# 8_sata.net
KiCad netlist of a schematic drawn in Altium Designer
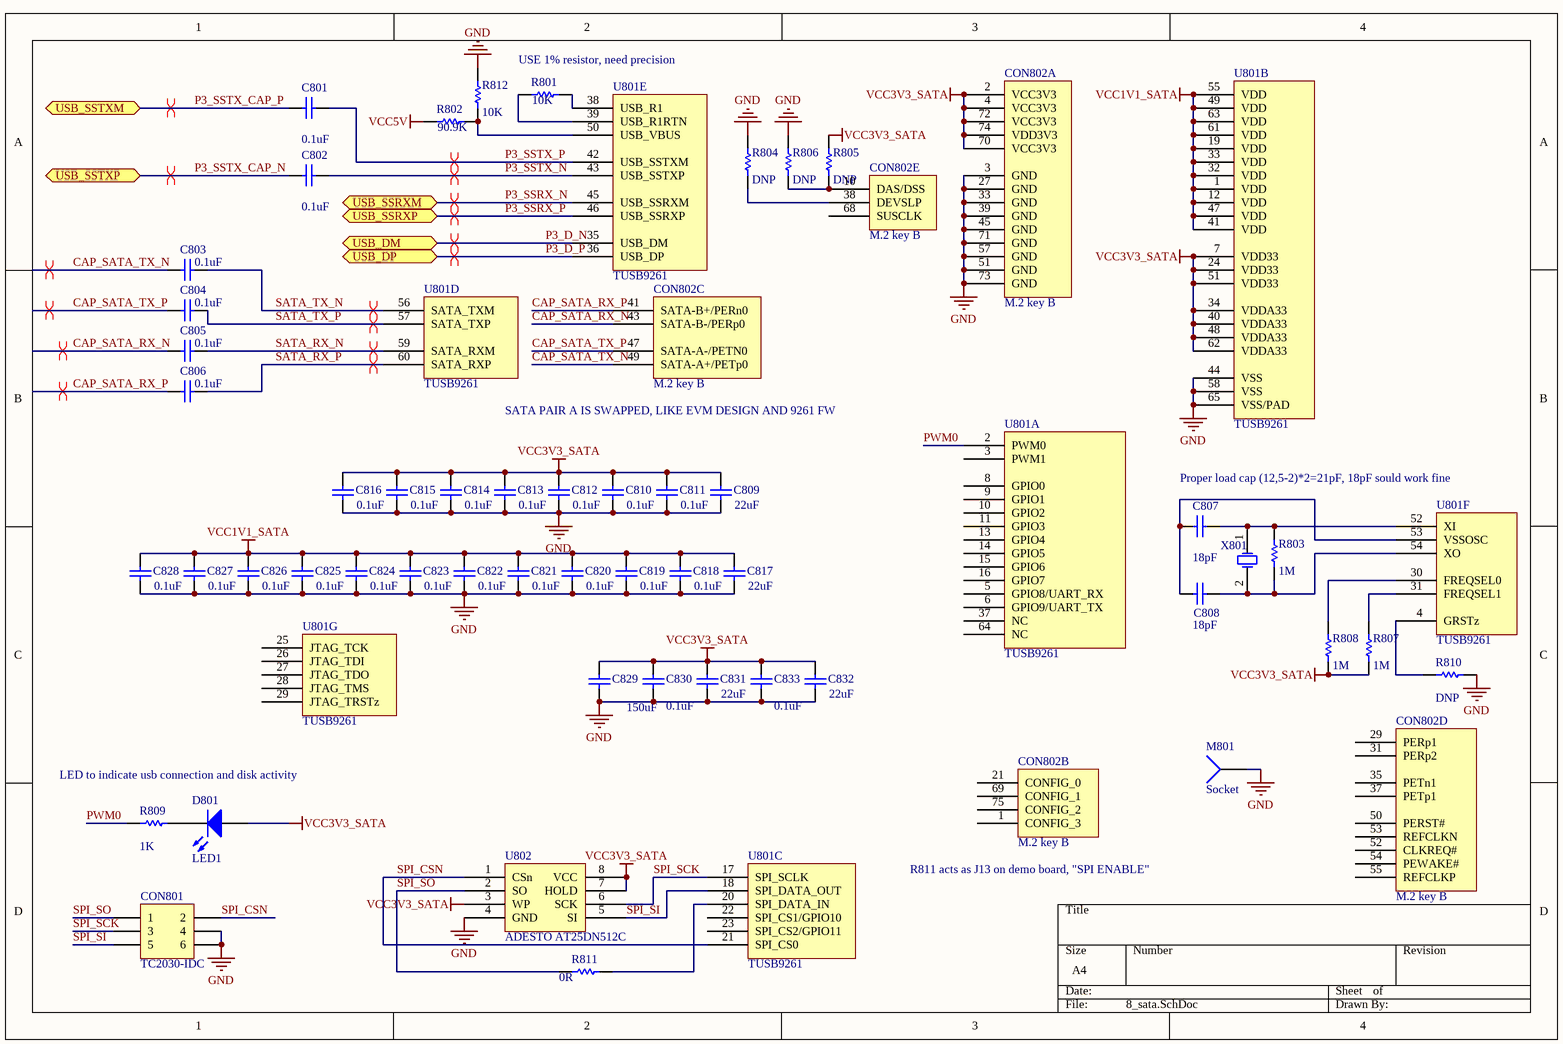
[diagram p0: 8_sata.SchDoc]

(export (version "E")
  (design (tool "Eeschema 10.0.6"))
  (components
    (comp (ref "C801")
      (value "0.1uF")
      (footprint "C0402[1005]")
      (description "Capacitor")
      (fields (field (name "MFG") "KEMET"))
      (libsource (lib "Miscellaneous Devices") (part "Cap"))
    )
    (comp (ref "C802")
      (value "0.1uF")
      (footprint "C0402[1005]")
      (description "Capacitor")
      (fields (field (name "MFG") "KEMET"))
      (libsource (lib "Miscellaneous Devices") (part "Cap"))
    )
    (comp (ref "C803")
      (value "0.1uF")
      (footprint "C0402[1005]")
      (description "Capacitor")
      (fields (field (name "MFG") "KEMET"))
      (libsource (lib "Miscellaneous Devices") (part "Cap"))
    )
    (comp (ref "C804")
      (value "0.1uF")
      (footprint "C0402[1005]")
      (description "Capacitor")
      (fields (field (name "MFG") "KEMET"))
      (libsource (lib "Miscellaneous Devices") (part "Cap"))
    )
    (comp (ref "C805")
      (value "0.1uF")
      (footprint "C0402[1005]")
      (description "Capacitor")
      (fields (field (name "MFG") "KEMET"))
      (libsource (lib "Miscellaneous Devices") (part "Cap"))
    )
    (comp (ref "C806")
      (value "0.1uF")
      (footprint "C0402[1005]")
      (description "Capacitor")
      (fields (field (name "MFG") "KEMET"))
      (libsource (lib "Miscellaneous Devices") (part "Cap"))
    )
    (comp (ref "C807")
      (value "18pF")
      (footprint "C0603[1608]")
      (description "Capacitor")
      (fields (field (name "MFG") "KEMET"))
      (libsource (lib "Miscellaneous Devices") (part "Cap"))
    )
    (comp (ref "C808")
      (value "18pF")
      (footprint "C0603[1608]")
      (description "Capacitor")
      (fields (field (name "MFG") "KEMET"))
      (libsource (lib "Miscellaneous Devices") (part "Cap"))
    )
    (comp (ref "C809")
      (value "22uF")
      (footprint "C1206[3216]")
      (description "Capacitor")
      (fields (field (name "MFG") "KEMET"))
      (libsource (lib "Miscellaneous Devices") (part "Cap"))
    )
    (comp (ref "C810")
      (value "0.1uF")
      (footprint "C0603[1608]")
      (description "Capacitor")
      (fields (field (name "MFG") "KEMET"))
      (libsource (lib "Miscellaneous Devices") (part "Cap"))
    )
    (comp (ref "C811")
      (value "0.1uF")
      (footprint "C0603[1608]")
      (description "Capacitor")
      (fields (field (name "MFG") "KEMET"))
      (libsource (lib "Miscellaneous Devices") (part "Cap"))
    )
    (comp (ref "C812")
      (value "0.1uF")
      (footprint "C0603[1608]")
      (description "Capacitor")
      (fields (field (name "MFG") "KEMET"))
      (libsource (lib "Miscellaneous Devices") (part "Cap"))
    )
    (comp (ref "C813")
      (value "0.1uF")
      (footprint "C0603[1608]")
      (description "Capacitor")
      (fields (field (name "MFG") "KEMET"))
      (libsource (lib "Miscellaneous Devices") (part "Cap"))
    )
    (comp (ref "C814")
      (value "0.1uF")
      (footprint "C0603[1608]")
      (description "Capacitor")
      (fields (field (name "MFG") "KEMET"))
      (libsource (lib "Miscellaneous Devices") (part "Cap"))
    )
    (comp (ref "C815")
      (value "0.1uF")
      (footprint "C0603[1608]")
      (description "Capacitor")
      (fields (field (name "MFG") "KEMET"))
      (libsource (lib "Miscellaneous Devices") (part "Cap"))
    )
    (comp (ref "C816")
      (value "0.1uF")
      (footprint "C0603[1608]")
      (description "Capacitor")
      (fields (field (name "MFG") "KEMET"))
      (libsource (lib "Miscellaneous Devices") (part "Cap"))
    )
    (comp (ref "C817")
      (value "22uF")
      (footprint "C1206[3216]")
      (description "Capacitor")
      (fields (field (name "MFG") "KEMET"))
      (libsource (lib "Miscellaneous Devices") (part "Cap"))
    )
    (comp (ref "C818")
      (value "0.1uF")
      (footprint "C0603[1608]")
      (description "Capacitor")
      (fields (field (name "MFG") "KEMET"))
      (libsource (lib "Miscellaneous Devices") (part "Cap"))
    )
    (comp (ref "C819")
      (value "0.1uF")
      (footprint "C0603[1608]")
      (description "Capacitor")
      (fields (field (name "MFG") "KEMET"))
      (libsource (lib "Miscellaneous Devices") (part "Cap"))
    )
    (comp (ref "C820")
      (value "0.1uF")
      (footprint "C0603[1608]")
      (description "Capacitor")
      (fields (field (name "MFG") "KEMET"))
      (libsource (lib "Miscellaneous Devices") (part "Cap"))
    )
    (comp (ref "C821")
      (value "0.1uF")
      (footprint "C0603[1608]")
      (description "Capacitor")
      (fields (field (name "MFG") "KEMET"))
      (libsource (lib "Miscellaneous Devices") (part "Cap"))
    )
    (comp (ref "C822")
      (value "0.1uF")
      (footprint "C0603[1608]")
      (description "Capacitor")
      (fields (field (name "MFG") "KEMET"))
      (libsource (lib "Miscellaneous Devices") (part "Cap"))
    )
    (comp (ref "C823")
      (value "0.1uF")
      (footprint "C0603[1608]")
      (description "Capacitor")
      (fields (field (name "MFG") "KEMET"))
      (libsource (lib "Miscellaneous Devices") (part "Cap"))
    )
    (comp (ref "C824")
      (value "0.1uF")
      (footprint "C0603[1608]")
      (description "Capacitor")
      (fields (field (name "MFG") "KEMET"))
      (libsource (lib "Miscellaneous Devices") (part "Cap"))
    )
    (comp (ref "C825")
      (value "0.1uF")
      (footprint "C0603[1608]")
      (description "Capacitor")
      (fields (field (name "MFG") "KEMET"))
      (libsource (lib "Miscellaneous Devices") (part "Cap"))
    )
    (comp (ref "C826")
      (value "0.1uF")
      (footprint "C0603[1608]")
      (description "Capacitor")
      (fields (field (name "MFG") "KEMET"))
      (libsource (lib "Miscellaneous Devices") (part "Cap"))
    )
    (comp (ref "C827")
      (value "0.1uF")
      (footprint "C0603[1608]")
      (description "Capacitor")
      (fields (field (name "MFG") "KEMET"))
      (libsource (lib "Miscellaneous Devices") (part "Cap"))
    )
    (comp (ref "C828")
      (value "0.1uF")
      (footprint "C0603[1608]")
      (description "Capacitor")
      (fields (field (name "MFG") "KEMET"))
      (libsource (lib "Miscellaneous Devices") (part "Cap"))
    )
    (comp (ref "C829")
      (value "150uF")
      (footprint "C_9G_9H")
      (description "Capacitor")
      (fields (field (name "MFG") "United Chemi-Con"))
      (libsource (lib "Miscellaneous Devices") (part "Cap"))
    )
    (comp (ref "C830")
      (value "0.1uF")
      (footprint "C0603[1608]")
      (description "Capacitor")
      (fields (field (name "MFG") "KEMET"))
      (libsource (lib "Miscellaneous Devices") (part "Cap"))
    )
    (comp (ref "C831")
      (value "22uF")
      (footprint "C1206[3216]")
      (description "Capacitor")
      (fields (field (name "MFG") "KEMET"))
      (libsource (lib "Miscellaneous Devices") (part "Cap"))
    )
    (comp (ref "C832")
      (value "22uF")
      (footprint "C1206[3216]")
      (description "Capacitor")
      (fields (field (name "MFG") "KEMET"))
      (libsource (lib "Miscellaneous Devices") (part "Cap"))
    )
    (comp (ref "C833")
      (value "0.1uF")
      (footprint "C0603[1608]")
      (description "Capacitor")
      (fields (field (name "MFG") "KEMET"))
      (libsource (lib "Miscellaneous Devices") (part "Cap"))
    )
    (comp (ref "CON801")
      (value "TC2030-IDC")
      (footprint "TC2030-IDC-NL")
      (description "Header, 3-Pin, Dual row")
      (fields (field (name "MFG") "No BOM"))
      (libsource (lib "Miscellaneous Connectors") (part "Header 3X2"))
    )
    (comp (ref "CON802")
      (value "M.2 key B")
      (footprint "Amphenol 10128796")
      (fields (field (name "MFG") "Amphenol ICC (FCI)"))
      (libsource (lib "lib") (part "M.2 key B"))
    )
    (comp (ref "D801")
      (value "LED1")
      (footprint "LED0603[1608]")
      (description "Typical RED GaAs LED")
      (fields (field (name "MFG") "Kingbright"))
      (libsource (lib "Miscellaneous Devices") (part "LED1"))
    )
    (comp (ref "M801")
      (value "Socket")
      (footprint "Wurth  9774060243R")
      (fields (field (name "MFG") "Würth Elektronik"))
      (libsource (lib "Miscellaneous Connectors") (part "Socket"))
    )
    (comp (ref "R801")
      (value "10K")
      (footprint "R0603[1608]")
      (description "Resistor")
      (fields (field (name "MFG") "Vishay Dale"))
      (libsource (lib "Miscellaneous Devices") (part "Res1"))
    )
    (comp (ref "R802")
      (value "90.9K")
      (footprint "R0603[1608]")
      (description "Resistor")
      (fields (field (name "MFG") "Vishay Dale"))
      (libsource (lib "Miscellaneous Devices") (part "Res1"))
    )
    (comp (ref "R803")
      (value "1M")
      (footprint "R0603[1608]")
      (description "Resistor")
      (fields (field (name "MFG") "Vishay Dale"))
      (libsource (lib "Miscellaneous Devices") (part "Res1"))
    )
    (comp (ref "R804")
      (value "DNP")
      (footprint "R0603[1608]")
      (description "Resistor")
      (fields (field (name "MFG") "Vishay Dale"))
      (libsource (lib "Miscellaneous Devices") (part "Res1"))
    )
    (comp (ref "R805")
      (value "DNP")
      (footprint "R0603[1608]")
      (description "Resistor")
      (fields (field (name "MFG") "Vishay Dale"))
      (libsource (lib "Miscellaneous Devices") (part "Res1"))
    )
    (comp (ref "R806")
      (value "DNP")
      (footprint "R0603[1608]")
      (description "Resistor")
      (fields (field (name "MFG") "Vishay Dale"))
      (libsource (lib "Miscellaneous Devices") (part "Res1"))
    )
    (comp (ref "R807")
      (value "1M")
      (footprint "R0603[1608]")
      (description "Resistor")
      (fields (field (name "MFG") "Vishay Dale"))
      (libsource (lib "Miscellaneous Devices") (part "Res1"))
    )
    (comp (ref "R808")
      (value "1M")
      (footprint "R0603[1608]")
      (description "Resistor")
      (fields (field (name "MFG") "Vishay Dale"))
      (libsource (lib "Miscellaneous Devices") (part "Res1"))
    )
    (comp (ref "R809")
      (value "1K")
      (footprint "R0603[1608]")
      (description "Resistor")
      (fields (field (name "MFG") "Vishay Dale"))
      (libsource (lib "Miscellaneous Devices") (part "Res1"))
    )
    (comp (ref "R810")
      (value "DNP")
      (footprint "R0603[1608]")
      (description "Resistor")
      (fields (field (name "MFG") "Vishay Dale"))
      (libsource (lib "Miscellaneous Devices") (part "Res1"))
    )
    (comp (ref "R811")
      (value "0R")
      (footprint "R0603[1608]")
      (description "Resistor")
      (fields (field (name "MFG") "Vishay Dale"))
      (libsource (lib "Miscellaneous Devices") (part "Res1"))
    )
    (comp (ref "R812")
      (value "10K")
      (footprint "R0603[1608]")
      (description "Resistor")
      (fields (field (name "MFG") "Vishay Dale"))
      (libsource (lib "Miscellaneous Devices") (part "Res1"))
    )
    (comp (ref "U801")
      (value "TUSB9261")
      (footprint "TUSB9261")
      (fields (field (name "MFG") "Texas Instruments"))
      (libsource (lib "lib") (part "TUSB9261"))
    )
    (comp (ref "U802")
      (value "ADESTO AT25DN512C")
      (footprint "ADESTO AT25DN512C -TSOP")
      (fields (field (name "MFG") "Adesto Technologies"))
      (libsource (lib "lib") (part "ADESTO AT25DN512C"))
    )
    (comp (ref "X801")
      (value "~")
      (footprint "CTS 445-series crystal")
      (description "Crystal Oscillator")
      (fields (field (name "MFG") "TXC CORPORATION"))
      (libsource (lib "Miscellaneous Devices") (part "XTAL"))
    )
  )
  (nets
    (net (code "1") (name "/CAP_SATA_RX_N") (class "Default")
      (node (ref "C805") (pin "2") (pinfunction "2_2") (pintype "passive"))
      (node (ref "CON802") (pin "43") (pinfunction "SATA-B-/PERp0_43") (pintype "passive"))
    )
    (net (code "2") (name "/CAP_SATA_RX_P") (class "Default")
      (node (ref "C806") (pin "2") (pinfunction "2_2") (pintype "passive"))
      (node (ref "CON802") (pin "41") (pinfunction "SATA-B+/PERn0_41") (pintype "passive"))
    )
    (net (code "3") (name "/CAP_SATA_TX_N") (class "Default")
      (node (ref "C803") (pin "2") (pinfunction "2_2") (pintype "passive"))
      (node (ref "CON802") (pin "49") (pinfunction "SATA-A+/PETp0_49") (pintype "passive"))
    )
    (net (code "4") (name "/CAP_SATA_TX_P") (class "Default")
      (node (ref "C804") (pin "2") (pinfunction "2_2") (pintype "passive"))
      (node (ref "CON802") (pin "47") (pinfunction "SATA-A-/PETN0_47") (pintype "passive"))
    )
    (net (code "5") (name "/P3_D_N") (class "Default")
      (node (ref "U801") (pin "35") (pinfunction "USB_DM_35") (pintype "passive"))
    )
    (net (code "6") (name "/P3_D_P") (class "Default")
      (node (ref "U801") (pin "36") (pinfunction "USB_DP_36") (pintype "passive"))
    )
    (net (code "7") (name "/P3_SSRX_N") (class "Default")
      (node (ref "U801") (pin "45") (pinfunction "USB_SSRXM_45") (pintype "passive"))
    )
    (net (code "8") (name "/P3_SSRX_P") (class "Default")
      (node (ref "U801") (pin "46") (pinfunction "USB_SSRXP_46") (pintype "passive"))
    )
    (net (code "9") (name "/P3_SSTX_CAP_N") (class "Default")
      (node (ref "C802") (pin "2") (pinfunction "2_2") (pintype "passive"))
    )
    (net (code "10") (name "/P3_SSTX_CAP_P") (class "Default")
      (node (ref "C801") (pin "2") (pinfunction "2_2") (pintype "passive"))
    )
    (net (code "11") (name "/P3_SSTX_N") (class "Default")
      (node (ref "C802") (pin "1") (pinfunction "1_1") (pintype "passive"))
      (node (ref "U801") (pin "43") (pinfunction "USB_SSTXP_43") (pintype "passive"))
    )
    (net (code "12") (name "/P3_SSTX_P") (class "Default")
      (node (ref "C801") (pin "1") (pinfunction "1_1") (pintype "passive"))
      (node (ref "U801") (pin "42") (pinfunction "USB_SSTXM_42") (pintype "passive"))
    )
    (net (code "13") (name "/PWM0") (class "Default")
      (node (ref "R809") (pin "1") (pinfunction "1_1") (pintype "passive"))
      (node (ref "U801") (pin "2") (pinfunction "PWM0_2") (pintype "passive"))
    )
    (net (code "14") (name "/SATA_RX_N") (class "Default")
      (node (ref "C805") (pin "1") (pinfunction "1_1") (pintype "passive"))
      (node (ref "U801") (pin "59") (pinfunction "SATA_RXM_59") (pintype "passive"))
    )
    (net (code "15") (name "/SATA_RX_P") (class "Default")
      (node (ref "C806") (pin "1") (pinfunction "1_1") (pintype "passive"))
      (node (ref "U801") (pin "60") (pinfunction "SATA_RXP_60") (pintype "passive"))
    )
    (net (code "16") (name "/SATA_TX_N") (class "Default")
      (node (ref "C803") (pin "1") (pinfunction "1_1") (pintype "passive"))
      (node (ref "U801") (pin "56") (pinfunction "SATA_TXM_56") (pintype "passive"))
    )
    (net (code "17") (name "/SATA_TX_P") (class "Default")
      (node (ref "C804") (pin "1") (pinfunction "1_1") (pintype "passive"))
      (node (ref "U801") (pin "57") (pinfunction "SATA_TXP_57") (pintype "passive"))
    )
    (net (code "18") (name "/SPI_CSN") (class "Default")
      (node (ref "CON801") (pin "2") (pinfunction "2_2") (pintype "passive"))
      (node (ref "U801") (pin "21") (pinfunction "SPI_CS0_21") (pintype "passive"))
      (node (ref "U802") (pin "1") (pinfunction "CSn_1") (pintype "passive"))
    )
    (net (code "19") (name "/SPI_SCK") (class "Default")
      (node (ref "CON801") (pin "3") (pinfunction "3_3") (pintype "passive"))
      (node (ref "U801") (pin "17") (pinfunction "SPI_SCLK_17") (pintype "passive"))
      (node (ref "U802") (pin "6") (pinfunction "SCK_6") (pintype "passive"))
    )
    (net (code "20") (name "/SPI_SI") (class "Default")
      (node (ref "CON801") (pin "5") (pinfunction "5_5") (pintype "passive"))
      (node (ref "U801") (pin "18") (pinfunction "SPI_DATA_OUT_18") (pintype "passive"))
      (node (ref "U802") (pin "5") (pinfunction "SI_5") (pintype "passive"))
    )
    (net (code "21") (name "/SPI_SO") (class "Default")
      (node (ref "CON801") (pin "1") (pinfunction "1_1") (pintype "passive"))
      (node (ref "R811") (pin "2") (pinfunction "2_2") (pintype "passive"))
      (node (ref "U802") (pin "2") (pinfunction "SO_2") (pintype "passive"))
    )
    (net (code "22") (name "GND") (class "Default")
      (node (ref "C809") (pin "1") (pinfunction "1_1") (pintype "passive"))
      (node (ref "C810") (pin "1") (pinfunction "1_1") (pintype "passive"))
      (node (ref "C811") (pin "1") (pinfunction "1_1") (pintype "passive"))
      (node (ref "C812") (pin "1") (pinfunction "1_1") (pintype "passive"))
      (node (ref "C813") (pin "1") (pinfunction "1_1") (pintype "passive"))
      (node (ref "C814") (pin "1") (pinfunction "1_1") (pintype "passive"))
      (node (ref "C815") (pin "1") (pinfunction "1_1") (pintype "passive"))
      (node (ref "C816") (pin "1") (pinfunction "1_1") (pintype "passive"))
      (node (ref "C817") (pin "1") (pinfunction "1_1") (pintype "passive"))
      (node (ref "C818") (pin "1") (pinfunction "1_1") (pintype "passive"))
      (node (ref "C819") (pin "1") (pinfunction "1_1") (pintype "passive"))
      (node (ref "C820") (pin "1") (pinfunction "1_1") (pintype "passive"))
      (node (ref "C821") (pin "1") (pinfunction "1_1") (pintype "passive"))
      (node (ref "C822") (pin "1") (pinfunction "1_1") (pintype "passive"))
      (node (ref "C823") (pin "1") (pinfunction "1_1") (pintype "passive"))
      (node (ref "C824") (pin "1") (pinfunction "1_1") (pintype "passive"))
      (node (ref "C825") (pin "1") (pinfunction "1_1") (pintype "passive"))
      (node (ref "C826") (pin "1") (pinfunction "1_1") (pintype "passive"))
      (node (ref "C827") (pin "1") (pinfunction "1_1") (pintype "passive"))
      (node (ref "C828") (pin "1") (pinfunction "1_1") (pintype "passive"))
      (node (ref "C829") (pin "1") (pinfunction "1_1") (pintype "passive"))
      (node (ref "C830") (pin "1") (pinfunction "1_1") (pintype "passive"))
      (node (ref "C831") (pin "1") (pinfunction "1_1") (pintype "passive"))
      (node (ref "C832") (pin "1") (pinfunction "1_1") (pintype "passive"))
      (node (ref "C833") (pin "1") (pinfunction "1_1") (pintype "passive"))
      (node (ref "CON801") (pin "4") (pinfunction "4_4") (pintype "passive"))
      (node (ref "CON801") (pin "6") (pinfunction "6_6") (pintype "passive"))
      (node (ref "CON802") (pin "27") (pinfunction "GND_27") (pintype "passive"))
      (node (ref "CON802") (pin "3") (pinfunction "GND_3") (pintype "passive"))
      (node (ref "CON802") (pin "33") (pinfunction "GND_33") (pintype "passive"))
      (node (ref "CON802") (pin "39") (pinfunction "GND_39") (pintype "passive"))
      (node (ref "CON802") (pin "45") (pinfunction "GND_45") (pintype "passive"))
      (node (ref "CON802") (pin "51") (pinfunction "GND_51") (pintype "passive"))
      (node (ref "CON802") (pin "57") (pinfunction "GND_57") (pintype "passive"))
      (node (ref "CON802") (pin "71") (pinfunction "GND_71") (pintype "passive"))
      (node (ref "CON802") (pin "73") (pinfunction "GND_73") (pintype "passive"))
      (node (ref "M801") (pin "1") (pinfunction "1_1") (pintype "passive"))
      (node (ref "R804") (pin "1") (pinfunction "1_1") (pintype "passive"))
      (node (ref "R806") (pin "1") (pinfunction "1_1") (pintype "passive"))
      (node (ref "R810") (pin "2") (pinfunction "2_2") (pintype "passive"))
      (node (ref "R812") (pin "1") (pinfunction "1_1") (pintype "passive"))
      (node (ref "U801") (pin "44") (pinfunction "VSS_44") (pintype "passive"))
      (node (ref "U801") (pin "58") (pinfunction "VSS_58") (pintype "passive"))
      (node (ref "U801") (pin "65") (pinfunction "VSS/PAD_65") (pintype "passive"))
      (node (ref "U802") (pin "4") (pinfunction "GND_4") (pintype "passive"))
    )
    (net (code "23") (name "Net-(CON802E-DAS{slash}DSS)") (class "Default")
      (node (ref "CON802") (pin "10") (pinfunction "DAS/DSS_10") (pintype "passive"))
      (node (ref "R805") (pin "2") (pinfunction "2_2") (pintype "passive"))
      (node (ref "R806") (pin "2") (pinfunction "2_2") (pintype "passive"))
    )
    (net (code "24") (name "Net-(CON802E-DEVSLP)") (class "Default")
      (node (ref "CON802") (pin "38") (pinfunction "DEVSLP_38") (pintype "passive"))
      (node (ref "R804") (pin "2") (pinfunction "2_2") (pintype "passive"))
    )
    (net (code "25") (name "Net-(D801-K)") (class "Default")
      (node (ref "D801") (pin "1") (pinfunction "K_1") (pintype "passive"))
      (node (ref "R809") (pin "2") (pinfunction "2_2") (pintype "passive"))
    )
    (net (code "26") (name "Net-(U801C-SPI_DATA_IN)") (class "Default")
      (node (ref "R811") (pin "1") (pinfunction "1_1") (pintype "passive"))
      (node (ref "U801") (pin "20") (pinfunction "SPI_DATA_IN_20") (pintype "passive"))
    )
    (net (code "27") (name "Net-(U801E-USB_R1)") (class "Default")
      (node (ref "R801") (pin "2") (pinfunction "2_2") (pintype "passive"))
      (node (ref "U801") (pin "38") (pinfunction "USB_R1_38") (pintype "passive"))
    )
    (net (code "28") (name "Net-(U801E-USB_R1RTN)") (class "Default")
      (node (ref "R801") (pin "1") (pinfunction "1_1") (pintype "passive"))
      (node (ref "U801") (pin "39") (pinfunction "USB_R1RTN_39") (pintype "passive"))
    )
    (net (code "29") (name "Net-(U801E-USB_VBUS)") (class "Default")
      (node (ref "R802") (pin "2") (pinfunction "2_2") (pintype "passive"))
      (node (ref "R812") (pin "2") (pinfunction "2_2") (pintype "passive"))
      (node (ref "U801") (pin "50") (pinfunction "USB_VBUS_50") (pintype "passive"))
    )
    (net (code "30") (name "Net-(U801F-FREQSEL0)") (class "Default")
      (node (ref "R808") (pin "1") (pinfunction "1_1") (pintype "passive"))
      (node (ref "U801") (pin "30") (pinfunction "FREQSEL0_30") (pintype "passive"))
    )
    (net (code "31") (name "Net-(U801F-FREQSEL1)") (class "Default")
      (node (ref "R807") (pin "1") (pinfunction "1_1") (pintype "passive"))
      (node (ref "U801") (pin "31") (pinfunction "FREQSEL1_31") (pintype "passive"))
    )
    (net (code "32") (name "Net-(U801F-GRSTz)") (class "Default")
      (node (ref "R810") (pin "1") (pinfunction "1_1") (pintype "passive"))
      (node (ref "U801") (pin "4") (pinfunction "GRSTz_4") (pintype "passive"))
    )
    (net (code "33") (name "Net-(U801F-VSSOSC)") (class "Default")
      (node (ref "C807") (pin "1") (pinfunction "1_1") (pintype "passive"))
      (node (ref "C808") (pin "1") (pinfunction "1_1") (pintype "passive"))
      (node (ref "U801") (pin "53") (pinfunction "VSSOSC_53") (pintype "passive"))
    )
    (net (code "34") (name "Net-(U801F-XI)") (class "Default")
      (node (ref "C807") (pin "2") (pinfunction "2_2") (pintype "passive"))
      (node (ref "R803") (pin "1") (pinfunction "1_1") (pintype "passive"))
      (node (ref "U801") (pin "52") (pinfunction "XI_52") (pintype "passive"))
      (node (ref "X801") (pin "1") (pinfunction "OSC1_1") (pintype "passive"))
    )
    (net (code "35") (name "Net-(U801F-XO)") (class "Default")
      (node (ref "C808") (pin "2") (pinfunction "2_2") (pintype "passive"))
      (node (ref "R803") (pin "2") (pinfunction "2_2") (pintype "passive"))
      (node (ref "U801") (pin "54") (pinfunction "XO_54") (pintype "passive"))
      (node (ref "X801") (pin "2") (pinfunction "OSC2_2") (pintype "passive"))
    )
    (net (code "36") (name "VCC1V1_SATA") (class "Default")
      (node (ref "C817") (pin "2") (pinfunction "2_2") (pintype "passive"))
      (node (ref "C818") (pin "2") (pinfunction "2_2") (pintype "passive"))
      (node (ref "C819") (pin "2") (pinfunction "2_2") (pintype "passive"))
      (node (ref "C820") (pin "2") (pinfunction "2_2") (pintype "passive"))
      (node (ref "C821") (pin "2") (pinfunction "2_2") (pintype "passive"))
      (node (ref "C822") (pin "2") (pinfunction "2_2") (pintype "passive"))
      (node (ref "C823") (pin "2") (pinfunction "2_2") (pintype "passive"))
      (node (ref "C824") (pin "2") (pinfunction "2_2") (pintype "passive"))
      (node (ref "C825") (pin "2") (pinfunction "2_2") (pintype "passive"))
      (node (ref "C826") (pin "2") (pinfunction "2_2") (pintype "passive"))
      (node (ref "C827") (pin "2") (pinfunction "2_2") (pintype "passive"))
      (node (ref "C828") (pin "2") (pinfunction "2_2") (pintype "passive"))
      (node (ref "U801") (pin "1") (pinfunction "VDD_1") (pintype "passive"))
      (node (ref "U801") (pin "12") (pinfunction "VDD_12") (pintype "passive"))
      (node (ref "U801") (pin "19") (pinfunction "VDD_19") (pintype "passive"))
      (node (ref "U801") (pin "32") (pinfunction "VDD_32") (pintype "passive"))
      (node (ref "U801") (pin "33") (pinfunction "VDD_33") (pintype "passive"))
      (node (ref "U801") (pin "41") (pinfunction "VDD_41") (pintype "passive"))
      (node (ref "U801") (pin "47") (pinfunction "VDD_47") (pintype "passive"))
      (node (ref "U801") (pin "49") (pinfunction "VDD_49") (pintype "passive"))
      (node (ref "U801") (pin "55") (pinfunction "VDD_55") (pintype "passive"))
      (node (ref "U801") (pin "61") (pinfunction "VDD_61") (pintype "passive"))
      (node (ref "U801") (pin "63") (pinfunction "VDD_63") (pintype "passive"))
    )
    (net (code "37") (name "VCC3V3_SATA") (class "Default")
      (node (ref "C809") (pin "2") (pinfunction "2_2") (pintype "passive"))
      (node (ref "C810") (pin "2") (pinfunction "2_2") (pintype "passive"))
      (node (ref "C811") (pin "2") (pinfunction "2_2") (pintype "passive"))
      (node (ref "C812") (pin "2") (pinfunction "2_2") (pintype "passive"))
      (node (ref "C813") (pin "2") (pinfunction "2_2") (pintype "passive"))
      (node (ref "C814") (pin "2") (pinfunction "2_2") (pintype "passive"))
      (node (ref "C815") (pin "2") (pinfunction "2_2") (pintype "passive"))
      (node (ref "C816") (pin "2") (pinfunction "2_2") (pintype "passive"))
      (node (ref "C829") (pin "2") (pinfunction "2_2") (pintype "passive"))
      (node (ref "C830") (pin "2") (pinfunction "2_2") (pintype "passive"))
      (node (ref "C831") (pin "2") (pinfunction "2_2") (pintype "passive"))
      (node (ref "C832") (pin "2") (pinfunction "2_2") (pintype "passive"))
      (node (ref "C833") (pin "2") (pinfunction "2_2") (pintype "passive"))
      (node (ref "CON802") (pin "2") (pinfunction "VCC3V3_2") (pintype "passive"))
      (node (ref "CON802") (pin "4") (pinfunction "VCC3V3_4") (pintype "passive"))
      (node (ref "CON802") (pin "70") (pinfunction "VCC3V3_70") (pintype "passive"))
      (node (ref "CON802") (pin "72") (pinfunction "VCC3V3_72") (pintype "passive"))
      (node (ref "CON802") (pin "74") (pinfunction "VDD3V3_74") (pintype "passive"))
      (node (ref "D801") (pin "2") (pinfunction "A_2") (pintype "passive"))
      (node (ref "R805") (pin "1") (pinfunction "1_1") (pintype "passive"))
      (node (ref "R807") (pin "2") (pinfunction "2_2") (pintype "passive"))
      (node (ref "R808") (pin "2") (pinfunction "2_2") (pintype "passive"))
      (node (ref "U801") (pin "24") (pinfunction "VDD33_24") (pintype "passive"))
      (node (ref "U801") (pin "34") (pinfunction "VDDA33_34") (pintype "passive"))
      (node (ref "U801") (pin "40") (pinfunction "VDDA33_40") (pintype "passive"))
      (node (ref "U801") (pin "48") (pinfunction "VDDA33_48") (pintype "passive"))
      (node (ref "U801") (pin "51") (pinfunction "VDD33_51") (pintype "passive"))
      (node (ref "U801") (pin "62") (pinfunction "VDDA33_62") (pintype "passive"))
      (node (ref "U801") (pin "7") (pinfunction "VDD33_7") (pintype "passive"))
      (node (ref "U802") (pin "3") (pinfunction "WP_3") (pintype "passive"))
      (node (ref "U802") (pin "7") (pinfunction "HOLD_7") (pintype "passive"))
      (node (ref "U802") (pin "8") (pinfunction "VCC_8") (pintype "passive"))
    )
    (net (code "38") (name "VCC5V") (class "Default")
      (node (ref "R802") (pin "1") (pinfunction "1_1") (pintype "passive"))
    )
    (net (code "39") (name "unconnected-(CON802B-CONFIG_0-Pad21)") (class "Default")
      (node (ref "CON802") (pin "21") (pinfunction "CONFIG_0_21") (pintype "passive"))
    )
    (net (code "40") (name "unconnected-(CON802B-CONFIG_1-Pad69)") (class "Default")
      (node (ref "CON802") (pin "69") (pinfunction "CONFIG_1_69") (pintype "passive"))
    )
    (net (code "41") (name "unconnected-(CON802B-CONFIG_2-Pad75)") (class "Default")
      (node (ref "CON802") (pin "75") (pinfunction "CONFIG_2_75") (pintype "passive"))
    )
    (net (code "42") (name "unconnected-(CON802B-CONFIG_3-Pad1)") (class "Default")
      (node (ref "CON802") (pin "1") (pinfunction "CONFIG_3_1") (pintype "passive"))
    )
    (net (code "43") (name "unconnected-(CON802D-CLKREQ#-Pad52)") (class "Default")
      (node (ref "CON802") (pin "52") (pinfunction "CLKREQ#_52") (pintype "passive"))
    )
    (net (code "44") (name "unconnected-(CON802D-PERST#-Pad50)") (class "Default")
      (node (ref "CON802") (pin "50") (pinfunction "PERST#_50") (pintype "passive"))
    )
    (net (code "45") (name "unconnected-(CON802D-PERp1-Pad29)") (class "Default")
      (node (ref "CON802") (pin "29") (pinfunction "PERp1_29") (pintype "passive"))
    )
    (net (code "46") (name "unconnected-(CON802D-PERp2-Pad31)") (class "Default")
      (node (ref "CON802") (pin "31") (pinfunction "PERp2_31") (pintype "passive"))
    )
    (net (code "47") (name "unconnected-(CON802D-PETn1-Pad35)") (class "Default")
      (node (ref "CON802") (pin "35") (pinfunction "PETn1_35") (pintype "passive"))
    )
    (net (code "48") (name "unconnected-(CON802D-PETp1-Pad37)") (class "Default")
      (node (ref "CON802") (pin "37") (pinfunction "PETp1_37") (pintype "passive"))
    )
    (net (code "49") (name "unconnected-(CON802D-PEWAKE#-Pad54)") (class "Default")
      (node (ref "CON802") (pin "54") (pinfunction "PEWAKE#_54") (pintype "passive"))
    )
    (net (code "50") (name "unconnected-(CON802D-REFCLKN-Pad53)") (class "Default")
      (node (ref "CON802") (pin "53") (pinfunction "REFCLKN_53") (pintype "passive"))
    )
    (net (code "51") (name "unconnected-(CON802D-REFCLKP-Pad55)") (class "Default")
      (node (ref "CON802") (pin "55") (pinfunction "REFCLKP_55") (pintype "passive"))
    )
    (net (code "52") (name "unconnected-(CON802E-SUSCLK-Pad68)") (class "Default")
      (node (ref "CON802") (pin "68") (pinfunction "SUSCLK_68") (pintype "passive"))
    )
    (net (code "53") (name "unconnected-(U801A-GPIO0-Pad8)") (class "Default")
      (node (ref "U801") (pin "8") (pinfunction "GPIO0_8") (pintype "passive"))
    )
    (net (code "54") (name "unconnected-(U801A-GPIO1-Pad9)") (class "Default")
      (node (ref "U801") (pin "9") (pinfunction "GPIO1_9") (pintype "passive"))
    )
    (net (code "55") (name "unconnected-(U801A-GPIO2-Pad10)") (class "Default")
      (node (ref "U801") (pin "10") (pinfunction "GPIO2_10") (pintype "passive"))
    )
    (net (code "56") (name "unconnected-(U801A-GPIO3-Pad11)") (class "Default")
      (node (ref "U801") (pin "11") (pinfunction "GPIO3_11") (pintype "passive"))
    )
    (net (code "57") (name "unconnected-(U801A-GPIO4-Pad13)") (class "Default")
      (node (ref "U801") (pin "13") (pinfunction "GPIO4_13") (pintype "passive"))
    )
    (net (code "58") (name "unconnected-(U801A-GPIO5-Pad14)") (class "Default")
      (node (ref "U801") (pin "14") (pinfunction "GPIO5_14") (pintype "passive"))
    )
    (net (code "59") (name "unconnected-(U801A-GPIO6-Pad15)") (class "Default")
      (node (ref "U801") (pin "15") (pinfunction "GPIO6_15") (pintype "passive"))
    )
    (net (code "60") (name "unconnected-(U801A-GPIO7-Pad16)") (class "Default")
      (node (ref "U801") (pin "16") (pinfunction "GPIO7_16") (pintype "passive"))
    )
    (net (code "61") (name "unconnected-(U801A-GPIO8{slash}UART_RX-Pad5)") (class "Default")
      (node (ref "U801") (pin "5") (pinfunction "GPIO8/UART_RX_5") (pintype "passive"))
    )
    (net (code "62") (name "unconnected-(U801A-GPIO9{slash}UART_TX-Pad6)") (class "Default")
      (node (ref "U801") (pin "6") (pinfunction "GPIO9/UART_TX_6") (pintype "passive"))
    )
    (net (code "63") (name "unconnected-(U801A-NC-Pad37)") (class "Default")
      (node (ref "U801") (pin "37") (pinfunction "NC_37") (pintype "passive"))
    )
    (net (code "64") (name "unconnected-(U801A-NC-Pad64)") (class "Default")
      (node (ref "U801") (pin "64") (pinfunction "NC_64") (pintype "passive"))
    )
    (net (code "65") (name "unconnected-(U801A-PWM1-Pad3)") (class "Default")
      (node (ref "U801") (pin "3") (pinfunction "PWM1_3") (pintype "passive"))
    )
    (net (code "66") (name "unconnected-(U801C-SPI_CS1{slash}GPIO10-Pad22)") (class "Default")
      (node (ref "U801") (pin "22") (pinfunction "SPI_CS1/GPIO10_22") (pintype "passive"))
    )
    (net (code "67") (name "unconnected-(U801C-SPI_CS2{slash}GPIO11-Pad23)") (class "Default")
      (node (ref "U801") (pin "23") (pinfunction "SPI_CS2/GPIO11_23") (pintype "passive"))
    )
    (net (code "68") (name "unconnected-(U801G-JTAG_TCK-Pad25)") (class "Default")
      (node (ref "U801") (pin "25") (pinfunction "JTAG_TCK_25") (pintype "passive"))
    )
    (net (code "69") (name "unconnected-(U801G-JTAG_TDI-Pad26)") (class "Default")
      (node (ref "U801") (pin "26") (pinfunction "JTAG_TDI_26") (pintype "passive"))
    )
    (net (code "70") (name "unconnected-(U801G-JTAG_TDO-Pad27)") (class "Default")
      (node (ref "U801") (pin "27") (pinfunction "JTAG_TDO_27") (pintype "passive"))
    )
    (net (code "71") (name "unconnected-(U801G-JTAG_TMS-Pad28)") (class "Default")
      (node (ref "U801") (pin "28") (pinfunction "JTAG_TMS_28") (pintype "passive"))
    )
    (net (code "72") (name "unconnected-(U801G-JTAG_TRSTz-Pad29)") (class "Default")
      (node (ref "U801") (pin "29") (pinfunction "JTAG_TRSTz_29") (pintype "passive"))
    )
  )
)
